# SH4-POWER.net
KiCad netlist of a schematic drawn in Altium Designer
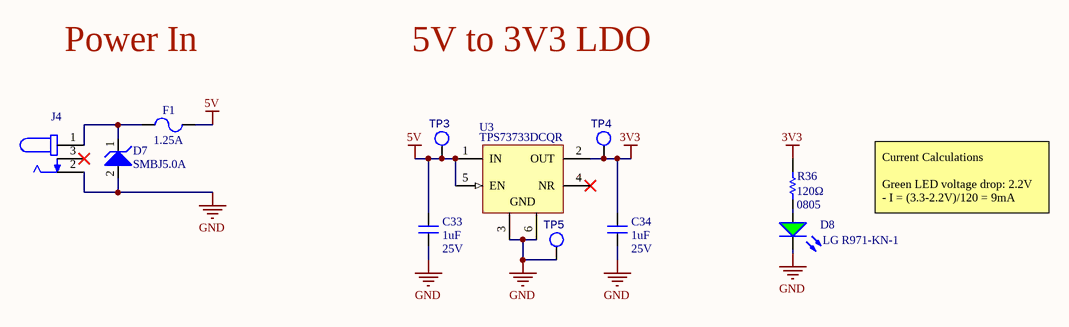
[diagram p0: SH4-POWER.SchDoc]

(export (version "E")
  (design (tool "Eeschema 10.0.6"))
  (components
    (comp (ref "C33")
      (value "~")
      (footprint "CAPC2012X140N")
      (description "CAP CER 1UF 25V X7R 0805")
      (fields
        (field (name "TOLERANCE") "10%")
        (field (name "CAPACITANCE") "1uF")
        (field (name "VOLTAGE RATING (DC)") "25V")
      )
      (libsource (lib "*") (part "CAP_1uF_25V_0805"))
    )
    (comp (ref "C34")
      (value "~")
      (footprint "CAPC2012X140N")
      (description "CAP CER 1UF 25V X7R 0805")
      (fields
        (field (name "TOLERANCE") "10%")
        (field (name "CAPACITANCE") "1uF")
        (field (name "VOLTAGE RATING (DC)") "25V")
      )
      (libsource (lib "*") (part "CAP_1uF_25V_0805"))
    )
    (comp (ref "D7")
      (value "TVS_DIODE_UNIDIR_5V")
      (footprint "TVS_DIODE_BIDIRECTIONAL")
      (description "TVS DIODE 5V 9.2V DO214AA")
      (fields (field (name "MANUFACTURER PART NUMBER 1") "SMBJ5.0A"))
      (libsource (lib "UWRT_Schematic_Library_2020") (part "TVS_DIODE_UNIDIR_5V"))
    )
    (comp (ref "D8")
      (value "LG R971-KN-1")
      (footprint "LED_0805_LINE")
      (description "LED GREEN DIFFUSED 0805 SMD")
      (libsource (lib "UWRT_Schematic_Library_2020") (part "DIO_LED_G"))
    )
    (comp (ref "F1")
      (value "FUSE_1.25A_1206")
      (footprint "FUSE_1206")
      (description "FUSE SMD 1.25A 63V")
      (fields (field (name "CURRENT RATING") "1.25A"))
      (libsource (lib "UWRT_Schematic_Library_2020") (part "FUSE_1.25A_1206"))
    )
    (comp (ref "J4")
      (value "PJ-102B")
      (footprint "CUI_PJ-102B")
      (description "2.5 x 6.5 mm, 2.5 A, Horizontal, Through Hole, Tapered Pins, Dc Power Jack Connector")
      (libsource (lib "UWRT_Schematic_Library_2020") (part "PJ-102B"))
    )
    (comp (ref "R36")
      (value "120")
      (footprint "RESC2012X60N")
      (description "RES SMD 120 OHM 1% 1/8W 0805")
      (fields (field (name "CASE CODE (IMPERIAL)") "0805") (field (name "RESISTANCE") "120Ω"))
      (libsource (lib "UWRT_Schematic_Library_2020") (part "RES_120Ω_0805"))
    )
    (comp (ref "TP3")
      (value "TESTPOINT_LOOP")
      (footprint "TESTPOINT_LOOP")
      (description "Loop testpoint through-hole pad")
      (libsource (lib "UWRT_Schematic_Library_2020") (part "TESTPOINT_LOOP"))
    )
    (comp (ref "TP4")
      (value "TESTPOINT_LOOP")
      (footprint "TESTPOINT_LOOP")
      (description "Loop testpoint through-hole pad")
      (libsource (lib "UWRT_Schematic_Library_2020") (part "TESTPOINT_LOOP"))
    )
    (comp (ref "TP5")
      (value "TESTPOINT_LOOP")
      (footprint "TESTPOINT_LOOP")
      (description "Loop testpoint through-hole pad")
      (libsource (lib "UWRT_Schematic_Library_2020") (part "TESTPOINT_LOOP"))
    )
    (comp (ref "U3")
      (value "TPS73733DCQR")
      (footprint "UWRT_Footprint_Library_2020:SOT-223-6")
      (description "IC REG LINEAR 3.3V 1A SOT223-6")
      (fields (field (name "MANUFACTURER") "Texas Instruments"))
      (libsource (lib "Altium Content Vault") (part "LDO_3.3V_1A"))
    )
  )
  (nets
    (net (code "1") (name "3V3") (class "Default")
      (node (ref "C34") (pin "2") (pinfunction "2_2") (pintype "passive"))
      (node (ref "R36") (pin "2") (pinfunction "2_2") (pintype "passive"))
      (node (ref "TP4") (pin "1") (pintype "passive"))
      (node (ref "U3") (pin "2") (pinfunction "OUT_2") (pintype "power_in"))
    )
    (net (code "2") (name "5V") (class "Default")
      (node (ref "C33") (pin "1") (pinfunction "1_1") (pintype "passive"))
      (node (ref "F1") (pin "2") (pinfunction "2_2") (pintype "passive"))
      (node (ref "TP3") (pin "1") (pintype "passive"))
      (node (ref "U3") (pin "1") (pinfunction "IN_1") (pintype "power_in"))
      (node (ref "U3") (pin "5") (pinfunction "EN_5") (pintype "input"))
    )
    (net (code "3") (name "GND") (class "Default")
      (node (ref "C33") (pin "2") (pinfunction "2_2") (pintype "passive"))
      (node (ref "C34") (pin "1") (pinfunction "1_1") (pintype "passive"))
      (node (ref "D7") (pin "2") (pinfunction "2_2") (pintype "passive"))
      (node (ref "D8") (pin "2") (pinfunction "K_2") (pintype "passive"))
      (node (ref "J4") (pin "2") (pinfunction "2_2") (pintype "passive"))
      (node (ref "TP5") (pin "1") (pintype "passive"))
      (node (ref "U3") (pin "3") (pinfunction "GND_3") (pintype "power_in"))
      (node (ref "U3") (pin "6") (pinfunction "GND_6") (pintype "power_in"))
    )
    (net (code "4") (name "Net-(D7-Pad1)") (class "Default")
      (node (ref "D7") (pin "1") (pinfunction "1_1") (pintype "passive"))
      (node (ref "F1") (pin "1") (pinfunction "1_1") (pintype "passive"))
      (node (ref "J4") (pin "1") (pinfunction "1_1") (pintype "passive"))
    )
    (net (code "5") (name "Net-(D8-A)") (class "Default")
      (node (ref "D8") (pin "1") (pinfunction "A_1") (pintype "passive"))
      (node (ref "R36") (pin "1") (pinfunction "1_1") (pintype "passive"))
    )
    (net (code "6") (name "unconnected-(J4-Pad3)") (class "Default")
      (node (ref "J4") (pin "3") (pinfunction "3_3") (pintype "passive+no_connect"))
    )
    (net (code "7") (name "unconnected-(U3-NR-Pad4)") (class "Default")
      (node (ref "U3") (pin "4") (pinfunction "NR_4") (pintype "passive+no_connect"))
    )
  )
)
